# lcd_buckler_mk_1.net
KiCad netlist of a schematic drawn in EAGLE
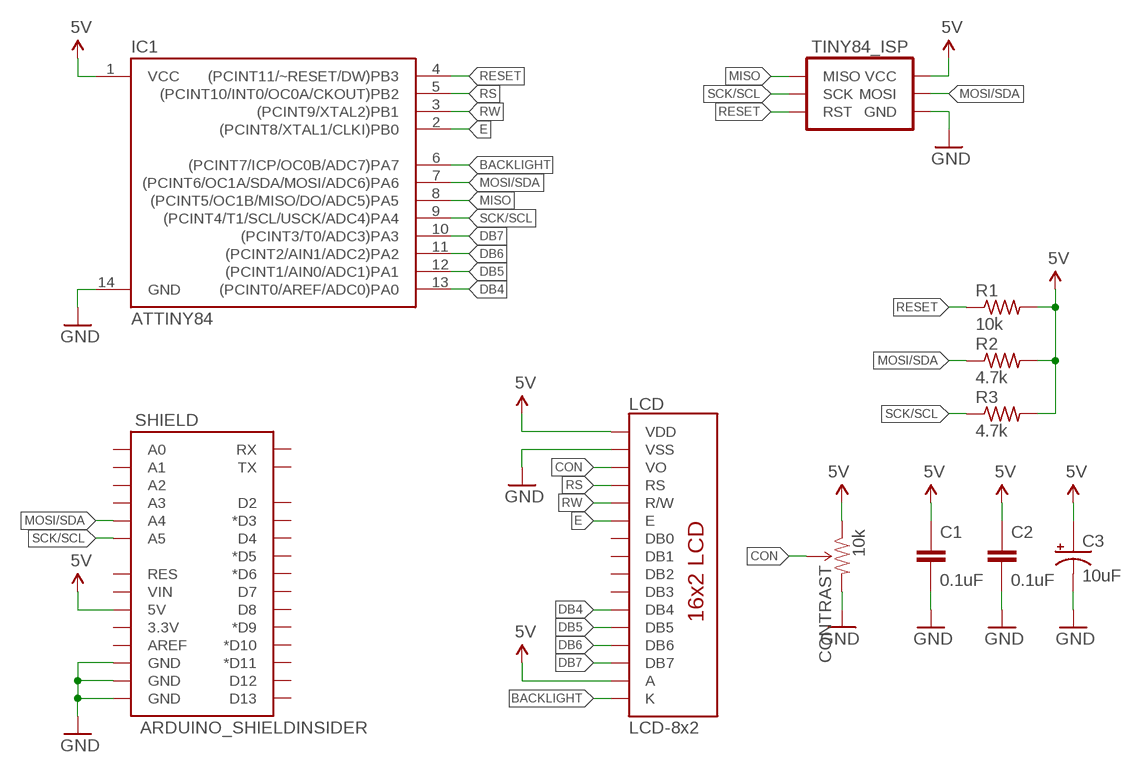
[diagram p0: schematic, sheet 1]

(export (version "E")
  (design (tool "Eeschema 10.0.6"))
  (components
    (comp (ref "C1")
      (value "0.1uF")
      (footprint "eagle-import:C025-024X044")
      (libsource (lib "eagle-import") (part "CAPACITOR-CERAMIC025-024X044"))
    )
    (comp (ref "C2")
      (value "0.1uF")
      (footprint "eagle-import:C025-024X044")
      (libsource (lib "eagle-import") (part "CAPACITOR-CERAMIC025-024X044"))
    )
    (comp (ref "C3")
      (value "10uF")
      (footprint "eagle-import:E2,5-5")
      (libsource (lib "eagle-import") (part "CAPACITOR-POLARIZEDE2.5-5"))
    )
    (comp (ref "CONTRAST")
      (value "10k")
      (footprint "eagle-import:TRIM_POT_PTH")
      (libsource (lib "eagle-import") (part "TRIMPOTPTH"))
    )
    (comp (ref "IC1")
      (value "ATTINY84")
      (footprint "eagle-import:DIL14")
      (libsource (lib "eagle-import") (part "ATTINY84ATTINY84-20PU"))
    )
    (comp (ref "LCD")
      (value "LCD-8x2")
      (footprint "eagle-import:LCD-8X2")
      (libsource (lib "eagle-import") (part "LCD-16X28X2"))
    )
    (comp (ref "R1")
      (value "10k")
      (footprint "eagle-import:RESISTOR-AXIAL-PTH-7.68MM")
      (libsource (lib "eagle-import") (part "RESISTORPTH-AXIAL-7.68MM"))
    )
    (comp (ref "R2")
      (value "4.7k")
      (footprint "eagle-import:RESISTOR-AXIAL-PTH-7.68MM")
      (libsource (lib "eagle-import") (part "RESISTORPTH-AXIAL-7.68MM"))
    )
    (comp (ref "R3")
      (value "4.7k")
      (footprint "eagle-import:RESISTOR-AXIAL-PTH-7.68MM")
      (libsource (lib "eagle-import") (part "RESISTORPTH-AXIAL-7.68MM"))
    )
    (comp (ref "SHIELD")
      (value "ARDUINO_SHIELDINSIDER")
      (footprint "eagle-import:ARDUINO_SHIELD_NOOUTLINE_INSIDE")
      (libsource (lib "eagle-import") (part "ARDUINO_SHIELDINSIDER"))
    )
    (comp (ref "TINY84_ISP")
      (value "AVR_SPI_PRG_6PTH")
      (footprint "eagle-import:2X3")
      (libsource (lib "eagle-import") (part "AVR_SPI_PRG_6PTH"))
    )
  )
  (nets
    (net (code "1") (name "5V") (class "Default")
      (node (ref "C1") (pin "1") (pinfunction "1_1") (pintype "passive"))
      (node (ref "C2") (pin "1") (pinfunction "1_1") (pintype "passive"))
      (node (ref "C3") (pin "+") (pinfunction "+_+") (pintype "passive"))
      (node (ref "CONTRAST") (pin "1") (pinfunction "CCW_1") (pintype "passive"))
      (node (ref "IC1") (pin "1") (pinfunction "VCC_1") (pintype "bidirectional"))
      (node (ref "LCD") (pin "15") (pinfunction "A_15") (pintype "power_in"))
      (node (ref "LCD") (pin "2") (pinfunction "VDD_2") (pintype "power_in"))
      (node (ref "R1") (pin "P$2") (pinfunction "2_P$2") (pintype "passive"))
      (node (ref "R2") (pin "P$2") (pinfunction "2_P$2") (pintype "passive"))
      (node (ref "R3") (pin "P$2") (pinfunction "2_P$2") (pintype "passive"))
      (node (ref "SHIELD") (pin "5V") (pinfunction "5V_5V") (pintype "bidirectional"))
      (node (ref "TINY84_ISP") (pin "2") (pinfunction "VCC_2") (pintype "passive"))
    )
    (net (code "2") (name "BACKLIGHT") (class "Default")
      (node (ref "IC1") (pin "6") (pinfunction "(PCINT7/ICP/OC0B/ADC7)PA7_6") (pintype "bidirectional"))
      (node (ref "LCD") (pin "16") (pinfunction "K_16") (pintype "power_in"))
    )
    (net (code "3") (name "CON") (class "Default")
      (node (ref "CONTRAST") (pin "2") (pinfunction "WIPER_2") (pintype "passive"))
      (node (ref "LCD") (pin "3") (pinfunction "VO_3") (pintype "bidirectional"))
    )
    (net (code "4") (name "DB4") (class "Default")
      (node (ref "IC1") (pin "13") (pinfunction "(PCINT0/AREF/ADC0)PA0_13") (pintype "bidirectional"))
      (node (ref "LCD") (pin "11") (pinfunction "DB4_11") (pintype "bidirectional"))
    )
    (net (code "5") (name "DB5") (class "Default")
      (node (ref "IC1") (pin "12") (pinfunction "(PCINT1/AIN0/ADC1)PA1_12") (pintype "bidirectional"))
      (node (ref "LCD") (pin "12") (pinfunction "DB5_12") (pintype "bidirectional"))
    )
    (net (code "6") (name "DB6") (class "Default")
      (node (ref "IC1") (pin "11") (pinfunction "(PCINT2/AIN1/ADC2)PA2_11") (pintype "bidirectional"))
      (node (ref "LCD") (pin "13") (pinfunction "DB6_13") (pintype "bidirectional"))
    )
    (net (code "7") (name "DB7") (class "Default")
      (node (ref "IC1") (pin "10") (pinfunction "(PCINT3/T0/ADC3)PA3_10") (pintype "bidirectional"))
      (node (ref "LCD") (pin "14") (pinfunction "DB7_14") (pintype "bidirectional"))
    )
    (net (code "8") (name "E") (class "Default")
      (node (ref "IC1") (pin "2") (pinfunction "(PCINT8/XTAL1/CLKI)PB0_2") (pintype "bidirectional"))
      (node (ref "LCD") (pin "6") (pinfunction "E_6") (pintype "input"))
    )
    (net (code "9") (name "GND") (class "Default")
      (node (ref "C1") (pin "2") (pinfunction "2_2") (pintype "passive"))
      (node (ref "C2") (pin "2") (pinfunction "2_2") (pintype "passive"))
      (node (ref "C3") (pin "-") (pinfunction "-_-") (pintype "passive"))
      (node (ref "CONTRAST") (pin "3") (pinfunction "CW_3") (pintype "passive"))
      (node (ref "IC1") (pin "14") (pinfunction "GND_14") (pintype "bidirectional"))
      (node (ref "LCD") (pin "1") (pinfunction "VSS_1") (pintype "power_in"))
      (node (ref "SHIELD") (pin "GND@0") (pinfunction "GND_GND@0") (pintype "bidirectional"))
      (node (ref "SHIELD") (pin "GND@1") (pinfunction "GND_GND@1") (pintype "bidirectional"))
      (node (ref "SHIELD") (pin "GND@2") (pinfunction "GND_GND@2") (pintype "bidirectional"))
      (node (ref "TINY84_ISP") (pin "6") (pinfunction "GND_6") (pintype "passive"))
    )
    (net (code "10") (name "MISO") (class "Default")
      (node (ref "IC1") (pin "8") (pinfunction "(PCINT5/OC1B/MISO/DO/ADC5)PA5_8") (pintype "bidirectional"))
      (node (ref "TINY84_ISP") (pin "1") (pinfunction "MISO_1") (pintype "passive"))
    )
    (net (code "11") (name "MOSI{slash}SDA") (class "Default")
      (node (ref "IC1") (pin "7") (pinfunction "(PCINT6/OC1A/SDA/MOSI/ADC6)PA6_7") (pintype "bidirectional"))
      (node (ref "R2") (pin "P$1") (pinfunction "1_P$1") (pintype "passive"))
      (node (ref "SHIELD") (pin "A4") (pinfunction "A4_A4") (pintype "bidirectional"))
      (node (ref "TINY84_ISP") (pin "4") (pinfunction "MOSI_4") (pintype "passive"))
    )
    (net (code "12") (name "RESET") (class "Default")
      (node (ref "IC1") (pin "4") (pinfunction "(PCINT11/~{RESET/DW})PB3_4") (pintype "bidirectional"))
      (node (ref "R1") (pin "P$1") (pinfunction "1_P$1") (pintype "passive"))
      (node (ref "TINY84_ISP") (pin "5") (pinfunction "RST_5") (pintype "passive"))
    )
    (net (code "13") (name "RS") (class "Default")
      (node (ref "IC1") (pin "5") (pinfunction "(PCINT10/INT0/OC0A/CKOUT)PB2_5") (pintype "bidirectional"))
      (node (ref "LCD") (pin "4") (pinfunction "RS_4") (pintype "input"))
    )
    (net (code "14") (name "RW") (class "Default")
      (node (ref "IC1") (pin "3") (pinfunction "(PCINT9/XTAL2)PB1_3") (pintype "bidirectional"))
      (node (ref "LCD") (pin "5") (pinfunction "R/W_5") (pintype "input"))
    )
    (net (code "15") (name "SCK{slash}SCL") (class "Default")
      (node (ref "IC1") (pin "9") (pinfunction "(PCINT4/T1/SCL/USCK/ADC4)PA4_9") (pintype "bidirectional"))
      (node (ref "R3") (pin "P$1") (pinfunction "1_P$1") (pintype "passive"))
      (node (ref "SHIELD") (pin "A5") (pinfunction "A5_A5") (pintype "bidirectional"))
      (node (ref "TINY84_ISP") (pin "3") (pinfunction "SCK_3") (pintype "passive"))
    )
    (net (code "16") (name "unconnected-(LCD-DB0-Pad7)") (class "Default")
      (node (ref "LCD") (pin "7") (pinfunction "DB0_7") (pintype "bidirectional"))
    )
    (net (code "17") (name "unconnected-(LCD-DB1-Pad8)") (class "Default")
      (node (ref "LCD") (pin "8") (pinfunction "DB1_8") (pintype "bidirectional"))
    )
    (net (code "18") (name "unconnected-(LCD-DB2-Pad9)") (class "Default")
      (node (ref "LCD") (pin "9") (pinfunction "DB2_9") (pintype "bidirectional"))
    )
    (net (code "19") (name "unconnected-(LCD-DB3-Pad10)") (class "Default")
      (node (ref "LCD") (pin "10") (pinfunction "DB3_10") (pintype "bidirectional"))
    )
    (net (code "20") (name "unconnected-(SHIELD-*D3-PadD3)") (class "Default")
      (node (ref "SHIELD") (pin "D3") (pinfunction "*D3_D3") (pintype "bidirectional"))
    )
    (net (code "21") (name "unconnected-(SHIELD-*D5-PadD5)") (class "Default")
      (node (ref "SHIELD") (pin "D5") (pinfunction "*D5_D5") (pintype "bidirectional"))
    )
    (net (code "22") (name "unconnected-(SHIELD-*D6-PadD6)") (class "Default")
      (node (ref "SHIELD") (pin "D6") (pinfunction "*D6_D6") (pintype "bidirectional"))
    )
    (net (code "23") (name "unconnected-(SHIELD-*D9-PadD9)") (class "Default")
      (node (ref "SHIELD") (pin "D9") (pinfunction "*D9_D9") (pintype "bidirectional"))
    )
    (net (code "24") (name "unconnected-(SHIELD-*D10-PadD10)") (class "Default")
      (node (ref "SHIELD") (pin "D10") (pinfunction "*D10_D10") (pintype "bidirectional"))
    )
    (net (code "25") (name "unconnected-(SHIELD-*D11-PadD11)") (class "Default")
      (node (ref "SHIELD") (pin "D11") (pinfunction "*D11_D11") (pintype "bidirectional"))
    )
    (net (code "26") (name "unconnected-(SHIELD-Pad3.3V)") (class "Default")
      (node (ref "SHIELD") (pin "3.3V") (pinfunction "3.3V_3.3V") (pintype "bidirectional"))
    )
    (net (code "27") (name "unconnected-(SHIELD-PadA0)") (class "Default")
      (node (ref "SHIELD") (pin "A0") (pinfunction "A0_A0") (pintype "bidirectional"))
    )
    (net (code "28") (name "unconnected-(SHIELD-PadA1)") (class "Default")
      (node (ref "SHIELD") (pin "A1") (pinfunction "A1_A1") (pintype "bidirectional"))
    )
    (net (code "29") (name "unconnected-(SHIELD-PadA2)") (class "Default")
      (node (ref "SHIELD") (pin "A2") (pinfunction "A2_A2") (pintype "bidirectional"))
    )
    (net (code "30") (name "unconnected-(SHIELD-PadA3)") (class "Default")
      (node (ref "SHIELD") (pin "A3") (pinfunction "A3_A3") (pintype "bidirectional"))
    )
    (net (code "31") (name "unconnected-(SHIELD-PadAREF)") (class "Default")
      (node (ref "SHIELD") (pin "AREF") (pinfunction "AREF_AREF") (pintype "bidirectional"))
    )
    (net (code "32") (name "unconnected-(SHIELD-PadD2)") (class "Default")
      (node (ref "SHIELD") (pin "D2") (pinfunction "D2_D2") (pintype "bidirectional"))
    )
    (net (code "33") (name "unconnected-(SHIELD-PadD4)") (class "Default")
      (node (ref "SHIELD") (pin "D4") (pinfunction "D4_D4") (pintype "bidirectional"))
    )
    (net (code "34") (name "unconnected-(SHIELD-PadD7)") (class "Default")
      (node (ref "SHIELD") (pin "D7") (pinfunction "D7_D7") (pintype "bidirectional"))
    )
    (net (code "35") (name "unconnected-(SHIELD-PadD8)") (class "Default")
      (node (ref "SHIELD") (pin "D8") (pinfunction "D8_D8") (pintype "bidirectional"))
    )
    (net (code "36") (name "unconnected-(SHIELD-PadD12)") (class "Default")
      (node (ref "SHIELD") (pin "D12") (pinfunction "D12_D12") (pintype "bidirectional"))
    )
    (net (code "37") (name "unconnected-(SHIELD-PadD13)") (class "Default")
      (node (ref "SHIELD") (pin "D13") (pinfunction "D13_D13") (pintype "bidirectional"))
    )
    (net (code "38") (name "unconnected-(SHIELD-PadRES)") (class "Default")
      (node (ref "SHIELD") (pin "RES") (pinfunction "RES_RES") (pintype "bidirectional"))
    )
    (net (code "39") (name "unconnected-(SHIELD-PadRX)") (class "Default")
      (node (ref "SHIELD") (pin "RX") (pinfunction "RX_RX") (pintype "bidirectional"))
    )
    (net (code "40") (name "unconnected-(SHIELD-PadTX)") (class "Default")
      (node (ref "SHIELD") (pin "TX") (pinfunction "TX_TX") (pintype "bidirectional"))
    )
    (net (code "41") (name "unconnected-(SHIELD-PadVIN)") (class "Default")
      (node (ref "SHIELD") (pin "VIN") (pinfunction "VIN_VIN") (pintype "bidirectional"))
    )
  )
)
